# Fubarino_SD_v15.net
KiCad netlist of a schematic drawn in EAGLE
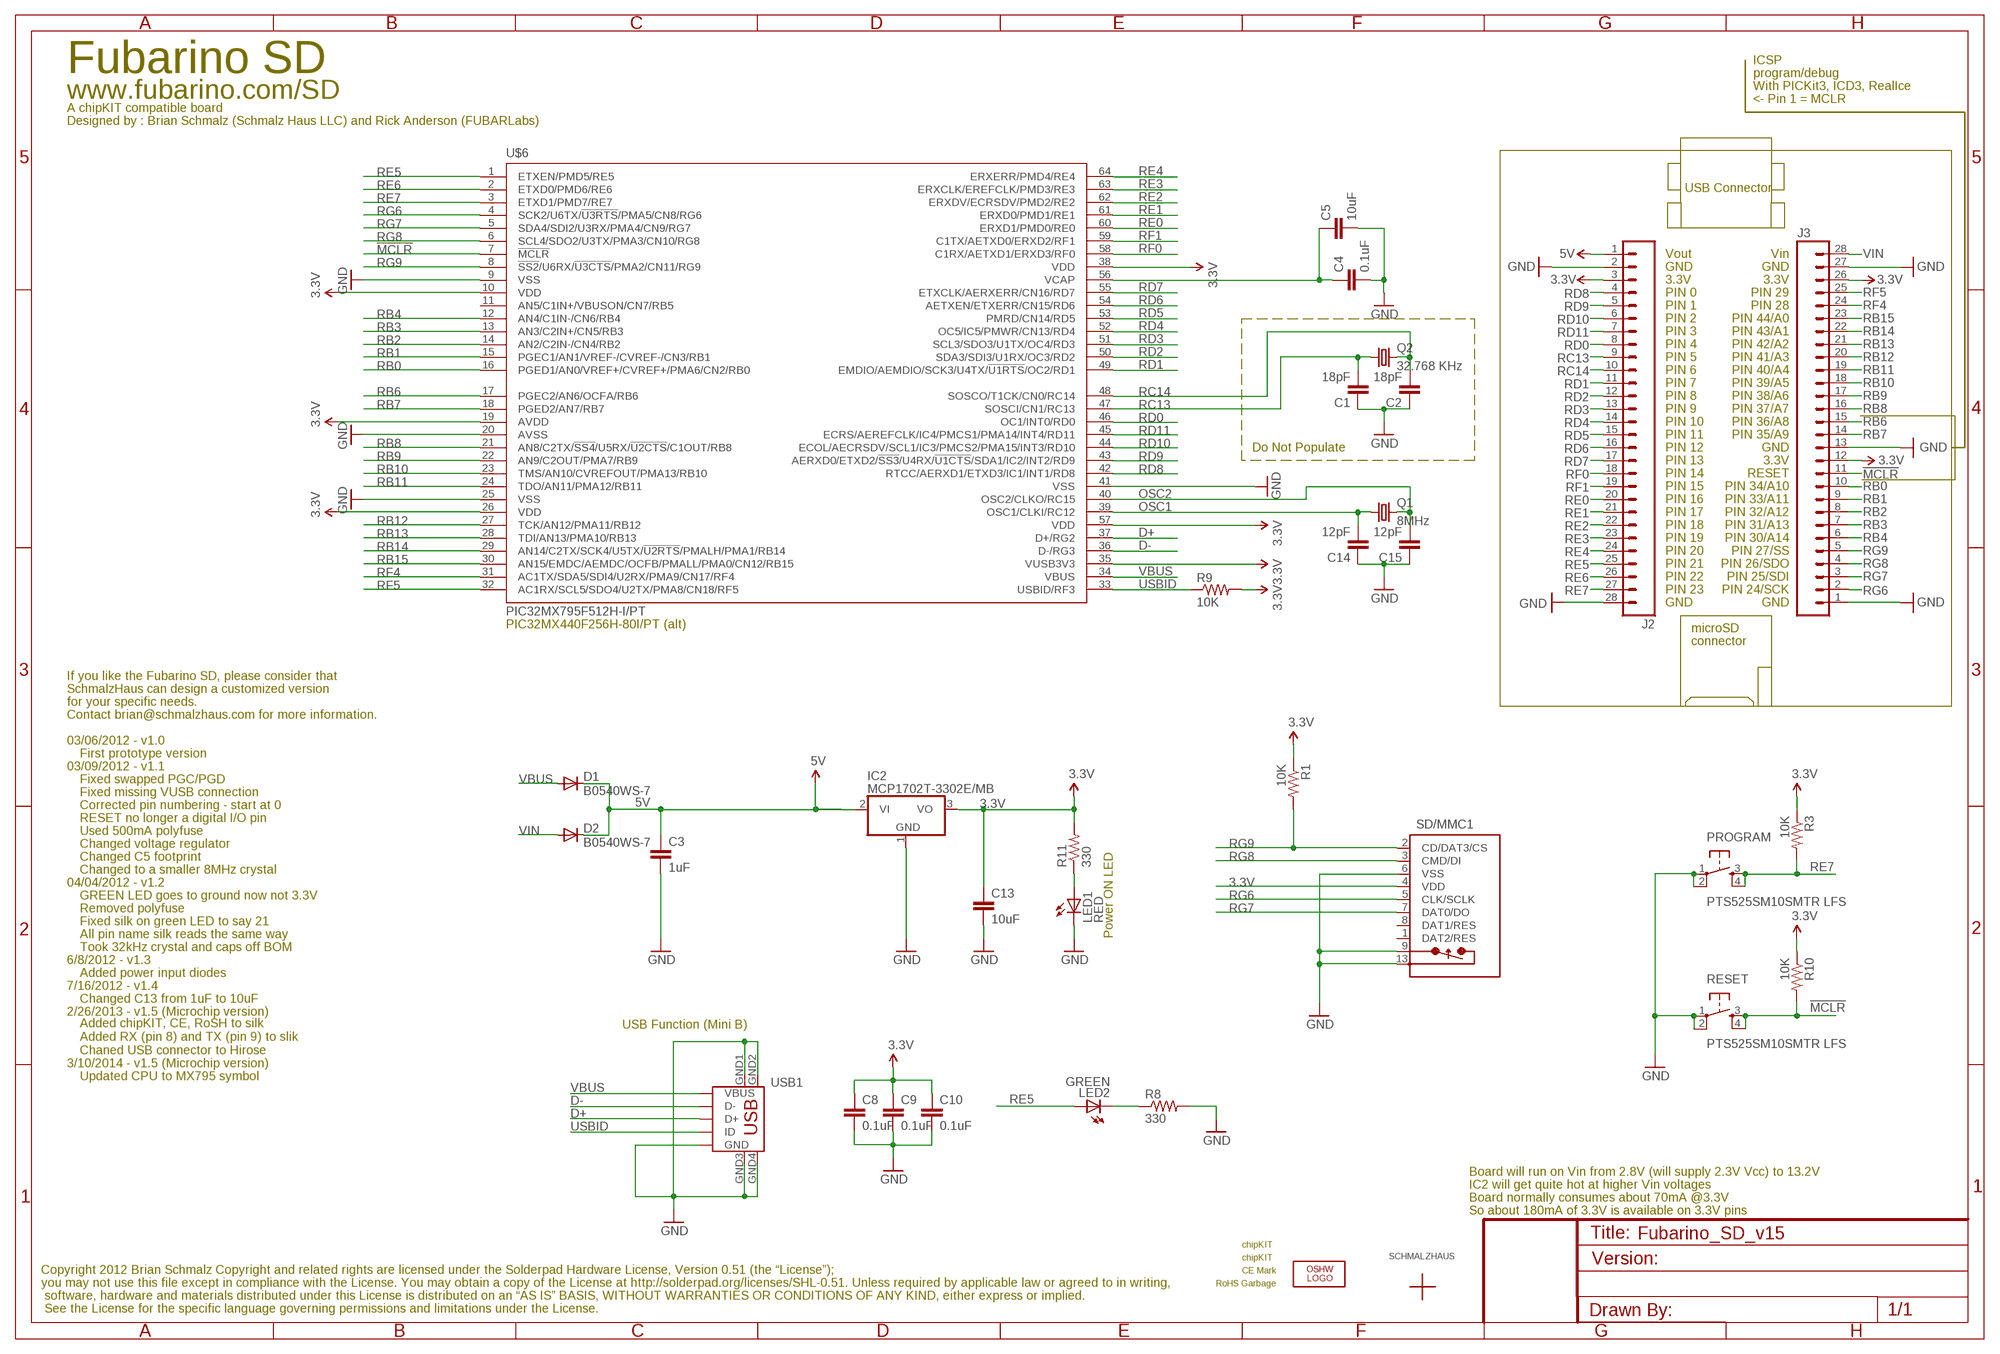
[diagram p0: schematic, sheet 1]

(export (version "E")
  (design (tool "Eeschema 10.0.6"))
  (components
    (comp (ref "C1")
      (value "18pF")
      (footprint "eagle-import:0603-CAP")
      (libsource (lib "eagle-import") (part "SparkFun_CAP0603-CAP"))
    )
    (comp (ref "C2")
      (value "18pF")
      (footprint "eagle-import:0603-CAP")
      (libsource (lib "eagle-import") (part "SparkFun_CAP0603-CAP"))
    )
    (comp (ref "C3")
      (value "1uF")
      (footprint "eagle-import:0603-CAP")
      (libsource (lib "eagle-import") (part "SparkFun_CAP0603-CAP"))
    )
    (comp (ref "C4")
      (value "0.1uF")
      (footprint "eagle-import:0603-CAP")
      (libsource (lib "eagle-import") (part "SparkFun_CAP0603-CAP"))
    )
    (comp (ref "C5")
      (value "10uF")
      (footprint "eagle-import:0805")
      (libsource (lib "eagle-import") (part "CAP0805"))
    )
    (comp (ref "C8")
      (value "0.1uF")
      (footprint "eagle-import:0603-CAP")
      (libsource (lib "eagle-import") (part "SparkFun_CAP0603-CAP"))
    )
    (comp (ref "C9")
      (value "0.1uF")
      (footprint "eagle-import:0603-CAP")
      (libsource (lib "eagle-import") (part "SparkFun_CAP0603-CAP"))
    )
    (comp (ref "C10")
      (value "0.1uF")
      (footprint "eagle-import:0603")
      (libsource (lib "eagle-import") (part "CAP0603"))
    )
    (comp (ref "C13")
      (value "10uF")
      (footprint "eagle-import:0805")
      (libsource (lib "eagle-import") (part "SparkFun02-20-08_CAP0805"))
    )
    (comp (ref "C14")
      (value "12pF")
      (footprint "eagle-import:0603-CAP")
      (libsource (lib "eagle-import") (part "SparkFun_CAP0603-CAP"))
    )
    (comp (ref "C15")
      (value "12pF")
      (footprint "eagle-import:0603-CAP")
      (libsource (lib "eagle-import") (part "SparkFun_CAP0603-CAP"))
    )
    (comp (ref "D1")
      (value "B0540WS-7")
      (footprint "eagle-import:SOD-323")
      (libsource (lib "eagle-import") (part "DIODESOD"))
    )
    (comp (ref "D2")
      (value "B0540WS-7")
      (footprint "eagle-import:SOD-323")
      (libsource (lib "eagle-import") (part "DIODESOD"))
    )
    (comp (ref "IC2")
      (value "MCP1702T-3302E/MB")
      (footprint "eagle-import:SOT89")
      (libsource (lib "eagle-import") (part "MCP1703MB33"))
    )
    (comp (ref "J2")
      (value "M28USEPIN1")
      (footprint "eagle-import:1X28")
      (libsource (lib "eagle-import") (part "M28USEPIN1"))
    )
    (comp (ref "J3")
      (value "M28NOPIN1")
      (footprint "eagle-import:1X28_NO_PIN_1")
      (libsource (lib "eagle-import") (part "M28NOPIN1"))
    )
    (comp (ref "LED1")
      (value "RED")
      (footprint "eagle-import:LED-0603")
      (libsource (lib "eagle-import") (part "LED0603"))
    )
    (comp (ref "LED2")
      (value "GREEN")
      (footprint "eagle-import:LED-0603")
      (libsource (lib "eagle-import") (part "LED0603"))
    )
    (comp (ref "LOGO1")
      (value "OSHW_LOGO_8MILX0070-NT")
      (footprint "eagle-import:OSHW_8X70_NOTEXT")
      (libsource (lib "eagle-import") (part "OSHW_LOGO_8MILX0070-NT"))
    )
    (comp (ref "PROGRAM")
      (value "PTS525SM10SMTR LFS")
      (footprint "eagle-import:TACTILE_SWITCH_SMD")
      (libsource (lib "eagle-import") (part "TAC_SWITCHSND"))
    )
    (comp (ref "Q1")
      (value "8MHz")
      (footprint "eagle-import:NX5032_5MM_3.2MM_CRYSTAL")
      (libsource (lib "eagle-import") (part "CRYSTALNX5032"))
    )
    (comp (ref "Q2")
      (value "32.768 KHz")
      (footprint "eagle-import:TC26H")
      (libsource (lib "eagle-import") (part "CRYSTALTC26H"))
    )
    (comp (ref "R1")
      (value "10K")
      (footprint "eagle-import:0603-RES")
      (libsource (lib "eagle-import") (part "RESISTOR0603-RES"))
    )
    (comp (ref "R3")
      (value "10K")
      (footprint "eagle-import:0603-RES")
      (libsource (lib "eagle-import") (part "RESISTOR0603-RES"))
    )
    (comp (ref "R8")
      (value "330")
      (footprint "eagle-import:0603-RES")
      (libsource (lib "eagle-import") (part "RESISTOR0603-RES"))
    )
    (comp (ref "R9")
      (value "10K")
      (footprint "eagle-import:0603-RES")
      (libsource (lib "eagle-import") (part "RESISTOR0603-RES"))
    )
    (comp (ref "R10")
      (value "10K")
      (footprint "eagle-import:0603-RES")
      (libsource (lib "eagle-import") (part "RESISTOR0603-RES"))
    )
    (comp (ref "R11")
      (value "330")
      (footprint "eagle-import:0603-RES")
      (libsource (lib "eagle-import") (part "RESISTOR0603-RES"))
    )
    (comp (ref "RESET")
      (value "PTS525SM10SMTR LFS")
      (footprint "eagle-import:TACTILE_SWITCH_SMD")
      (libsource (lib "eagle-import") (part "TAC_SWITCHSND"))
    )
    (comp (ref "SD/MMC1")
      (value "MICRO_SD/MMC_CP_NEWTFC-WPAPR-08")
      (footprint "eagle-import:TFC-WPAPR-08")
      (libsource (lib "eagle-import") (part "MICRO_SD/MMC_CP_NEWTFC-WPAPR-08"))
    )
    (comp (ref "U$1")
      (value "SCHMALZHAUSSCHMALZHAUS_SMALL")
      (footprint "eagle-import:SCHMALZHAUS_SMALL")
      (libsource (lib "eagle-import") (part "SCHMALZHAUSSCHMALZHAUS_SMALL"))
    )
    (comp (ref "U$2")
      (value "CE_MARK5MM")
      (footprint "eagle-import:CE_5MM")
      (libsource (lib "eagle-import") (part "CE_MARK5MM"))
    )
    (comp (ref "U$3")
      (value "ROHS_GARBAGE")
      (footprint "eagle-import:ROHS_GARBAGE_5MM")
      (libsource (lib "eagle-import") (part "ROHS_GARBAGE"))
    )
    (comp (ref "U$4")
      (value "CHIPKIT2MM")
      (footprint "eagle-import:CHIPKIT_2MM")
      (libsource (lib "eagle-import") (part "CHIPKIT2MM"))
    )
    (comp (ref "U$5")
      (value "CHIPKIT2MM")
      (footprint "eagle-import:CHIPKIT_2MM")
      (libsource (lib "eagle-import") (part "CHIPKIT2MM"))
    )
    (comp (ref "U$6")
      (value "PIC32MX795F512H-I/PT")
      (footprint "eagle-import:TQFP64-10X10")
      (libsource (lib "eagle-import") (part "PIC32MX795F512H-I/PT"))
    )
    (comp (ref "USB1")
      (value "MINI_USB9SMALLER_CREAM")
      (footprint "eagle-import:USB_MINI_9PIN-SMALLER_CREAM")
      (libsource (lib "eagle-import") (part "MINI_USB9SMALLER_CREAM"))
    )
  )
  (nets
    (net (code "1") (name "/D+") (class "Default")
      (node (ref "U$6") (pin "37") (pinfunction "D+/RG2_37") (pintype "bidirectional"))
      (node (ref "USB1") (pin "D+") (pinfunction "D+_D+") (pintype "input"))
    )
    (net (code "2") (name "/D-") (class "Default")
      (node (ref "U$6") (pin "36") (pinfunction "D-/RG3_36") (pintype "bidirectional"))
      (node (ref "USB1") (pin "D-") (pinfunction "D-_D-") (pintype "input"))
    )
    (net (code "3") (name "/OSC1") (class "Default")
      (node (ref "C14") (pin "2") (pinfunction "2_2") (pintype "passive"))
      (node (ref "Q1") (pin "1") (pinfunction "1_1") (pintype "passive"))
      (node (ref "U$6") (pin "39") (pinfunction "OSC1/CLKI/RC12_39") (pintype "bidirectional"))
    )
    (net (code "4") (name "/OSC2") (class "Default")
      (node (ref "C15") (pin "2") (pinfunction "2_2") (pintype "passive"))
      (node (ref "Q1") (pin "2") (pinfunction "2_2") (pintype "passive"))
      (node (ref "U$6") (pin "40") (pinfunction "OSC2/CLKO/RC15_40") (pintype "bidirectional"))
    )
    (net (code "5") (name "/RB0") (class "Default")
      (node (ref "J3") (pin "10") (pinfunction "10_10") (pintype "passive"))
      (node (ref "U$6") (pin "16") (pinfunction "PGED1/AN0/VREF+/CVREF+/PMA6/CN2/RB0_16") (pintype "bidirectional"))
    )
    (net (code "6") (name "/RB1") (class "Default")
      (node (ref "J3") (pin "9") (pinfunction "9_9") (pintype "passive"))
      (node (ref "U$6") (pin "15") (pinfunction "PGEC1/AN1/VREF-/CVREF-/CN3/RB1_15") (pintype "bidirectional"))
    )
    (net (code "7") (name "/RB2") (class "Default")
      (node (ref "J3") (pin "8") (pinfunction "8_8") (pintype "passive"))
      (node (ref "U$6") (pin "14") (pinfunction "AN2/C2IN-/CN4/RB2_14") (pintype "bidirectional"))
    )
    (net (code "8") (name "/RB3") (class "Default")
      (node (ref "J3") (pin "7") (pinfunction "7_7") (pintype "passive"))
      (node (ref "U$6") (pin "13") (pinfunction "AN3/C2IN+/CN5/RB3_13") (pintype "bidirectional"))
    )
    (net (code "9") (name "/RB4") (class "Default")
      (node (ref "J3") (pin "6") (pinfunction "6_6") (pintype "passive"))
      (node (ref "U$6") (pin "12") (pinfunction "AN4/C1IN-/CN6/RB4_12") (pintype "bidirectional"))
    )
    (net (code "10") (name "/RB6") (class "Default")
      (node (ref "J3") (pin "15") (pinfunction "15_15") (pintype "passive"))
      (node (ref "U$6") (pin "17") (pinfunction "PGEC2/AN6/OCFA/RB6_17") (pintype "bidirectional"))
    )
    (net (code "11") (name "/RB7") (class "Default")
      (node (ref "J3") (pin "14") (pinfunction "14_14") (pintype "passive"))
      (node (ref "U$6") (pin "18") (pinfunction "PGED2/AN7/RB7_18") (pintype "bidirectional"))
    )
    (net (code "12") (name "/RB8") (class "Default")
      (node (ref "J3") (pin "16") (pinfunction "16_16") (pintype "passive"))
      (node (ref "U$6") (pin "21") (pinfunction "AN8/C2TX/~{SS4}/U5RX/~{U2CTS}/C1OUT/RB8_21") (pintype "bidirectional"))
    )
    (net (code "13") (name "/RB9") (class "Default")
      (node (ref "J3") (pin "17") (pinfunction "17_17") (pintype "passive"))
      (node (ref "U$6") (pin "22") (pinfunction "AN9/C2OUT/PMA7/RB9_22") (pintype "bidirectional"))
    )
    (net (code "14") (name "/RB10") (class "Default")
      (node (ref "J3") (pin "18") (pinfunction "18_18") (pintype "passive"))
      (node (ref "U$6") (pin "23") (pinfunction "TMS/AN10/CVREFOUT/PMA13/RB10_23") (pintype "input"))
    )
    (net (code "15") (name "/RB11") (class "Default")
      (node (ref "J3") (pin "19") (pinfunction "19_19") (pintype "passive"))
      (node (ref "U$6") (pin "24") (pinfunction "TDO/AN11/PMA12/RB11_24") (pintype "bidirectional"))
    )
    (net (code "16") (name "/RB12") (class "Default")
      (node (ref "J3") (pin "20") (pinfunction "20_20") (pintype "passive"))
      (node (ref "U$6") (pin "27") (pinfunction "TCK/AN12/PMA11/RB12_27") (pintype "input"))
    )
    (net (code "17") (name "/RB13") (class "Default")
      (node (ref "J3") (pin "21") (pinfunction "21_21") (pintype "passive"))
      (node (ref "U$6") (pin "28") (pinfunction "TDI/AN13/PMA10/RB13_28") (pintype "input"))
    )
    (net (code "18") (name "/RB14") (class "Default")
      (node (ref "J3") (pin "22") (pinfunction "22_22") (pintype "passive"))
      (node (ref "U$6") (pin "29") (pinfunction "AN14/C2TX/SCK4/U5TX/~{U2RTS}/PMALH/PMA1/RB14_29") (pintype "bidirectional"))
    )
    (net (code "19") (name "/RB15") (class "Default")
      (node (ref "J3") (pin "23") (pinfunction "23_23") (pintype "passive"))
      (node (ref "U$6") (pin "30") (pinfunction "AN15/EMDC/AEMDC/OCFB/PMALL/PMA0/CN12/RB15_30") (pintype "bidirectional"))
    )
    (net (code "20") (name "/RC13") (class "Default")
      (node (ref "C1") (pin "2") (pinfunction "2_2") (pintype "passive"))
      (node (ref "J2") (pin "9") (pinfunction "9_9") (pintype "passive"))
      (node (ref "Q2") (pin "1") (pinfunction "1_1") (pintype "passive"))
      (node (ref "U$6") (pin "47") (pinfunction "SOSCI/CN1/RC13_47") (pintype "bidirectional"))
    )
    (net (code "21") (name "/RC14") (class "Default")
      (node (ref "C2") (pin "2") (pinfunction "2_2") (pintype "passive"))
      (node (ref "J2") (pin "10") (pinfunction "10_10") (pintype "passive"))
      (node (ref "Q2") (pin "2") (pinfunction "2_2") (pintype "passive"))
      (node (ref "U$6") (pin "48") (pinfunction "SOSCO/T1CK/CN0/RC14_48") (pintype "bidirectional"))
    )
    (net (code "22") (name "/RD0") (class "Default")
      (node (ref "J2") (pin "8") (pinfunction "8_8") (pintype "passive"))
      (node (ref "U$6") (pin "46") (pinfunction "OC1/INT0/RD0_46") (pintype "bidirectional"))
    )
    (net (code "23") (name "/RD1") (class "Default")
      (node (ref "J2") (pin "11") (pinfunction "11_11") (pintype "passive"))
      (node (ref "U$6") (pin "49") (pinfunction "EMDIO/AEMDIO/SCK3/U4TX/~{U1RTS}/OC2/RD1_49") (pintype "bidirectional"))
    )
    (net (code "24") (name "/RD2") (class "Default")
      (node (ref "J2") (pin "12") (pinfunction "12_12") (pintype "passive"))
      (node (ref "U$6") (pin "50") (pinfunction "SDA3/SDI3/U1RX/OC3/RD2_50") (pintype "bidirectional"))
    )
    (net (code "25") (name "/RD3") (class "Default")
      (node (ref "J2") (pin "13") (pinfunction "13_13") (pintype "passive"))
      (node (ref "U$6") (pin "51") (pinfunction "SCL3/SDO3/U1TX/OC4/RD3_51") (pintype "bidirectional"))
    )
    (net (code "26") (name "/RD4") (class "Default")
      (node (ref "J2") (pin "14") (pinfunction "14_14") (pintype "passive"))
      (node (ref "U$6") (pin "52") (pinfunction "OC5/IC5/PMWR/CN13/RD4_52") (pintype "bidirectional"))
    )
    (net (code "27") (name "/RD5") (class "Default")
      (node (ref "J2") (pin "15") (pinfunction "15_15") (pintype "passive"))
      (node (ref "U$6") (pin "53") (pinfunction "PMRD/CN14/RD5_53") (pintype "bidirectional"))
    )
    (net (code "28") (name "/RD6") (class "Default")
      (node (ref "J2") (pin "16") (pinfunction "16_16") (pintype "passive"))
      (node (ref "U$6") (pin "54") (pinfunction "AETXEN/ETXERR/CN15/RD6_54") (pintype "bidirectional"))
    )
    (net (code "29") (name "/RD7") (class "Default")
      (node (ref "J2") (pin "17") (pinfunction "17_17") (pintype "passive"))
      (node (ref "U$6") (pin "55") (pinfunction "ETXCLK/AERXERR/CN16/RD7_55") (pintype "bidirectional"))
    )
    (net (code "30") (name "/RD8") (class "Default")
      (node (ref "J2") (pin "4") (pinfunction "4_4") (pintype "passive"))
      (node (ref "U$6") (pin "42") (pinfunction "RTCC/AERXD1/ETXD3/IC1/INT1/RD8_42") (pintype "bidirectional"))
    )
    (net (code "31") (name "/RD9") (class "Default")
      (node (ref "J2") (pin "5") (pinfunction "5_5") (pintype "passive"))
      (node (ref "U$6") (pin "43") (pinfunction "AERXD0/ETXD2/~{SS3}/U4RX/~{U1CTS}/SDA1/IC2/INT2/RD9_43") (pintype "bidirectional"))
    )
    (net (code "32") (name "/RD10") (class "Default")
      (node (ref "J2") (pin "6") (pinfunction "6_6") (pintype "passive"))
      (node (ref "U$6") (pin "44") (pinfunction "ECOL/AECRSDV/SCL1/IC3/PMCS2/PMA15/INT3/RD10_44") (pintype "bidirectional"))
    )
    (net (code "33") (name "/RD11") (class "Default")
      (node (ref "J2") (pin "7") (pinfunction "7_7") (pintype "passive"))
      (node (ref "U$6") (pin "45") (pinfunction "ECRS/AEREFCLK/IC4/PMCS1/PMA14/INT4/RD11_45") (pintype "bidirectional"))
    )
    (net (code "34") (name "/RE0") (class "Default")
      (node (ref "J2") (pin "20") (pinfunction "20_20") (pintype "passive"))
      (node (ref "U$6") (pin "60") (pinfunction "ERXD1/PMD0/RE0_60") (pintype "bidirectional"))
    )
    (net (code "35") (name "/RE1") (class "Default")
      (node (ref "J2") (pin "21") (pinfunction "21_21") (pintype "passive"))
      (node (ref "U$6") (pin "61") (pinfunction "ERXD0/PMD1/RE1_61") (pintype "bidirectional"))
    )
    (net (code "36") (name "/RE2") (class "Default")
      (node (ref "J2") (pin "22") (pinfunction "22_22") (pintype "passive"))
      (node (ref "U$6") (pin "62") (pinfunction "ERXDV/ECRSDV/PMD2/RE2_62") (pintype "bidirectional"))
    )
    (net (code "37") (name "/RE3") (class "Default")
      (node (ref "J2") (pin "23") (pinfunction "23_23") (pintype "passive"))
      (node (ref "U$6") (pin "63") (pinfunction "ERXCLK/EREFCLK/PMD3/RE3_63") (pintype "bidirectional"))
    )
    (net (code "38") (name "/RE4") (class "Default")
      (node (ref "J2") (pin "24") (pinfunction "24_24") (pintype "passive"))
      (node (ref "U$6") (pin "64") (pinfunction "ERXERR/PMD4/RE4_64") (pintype "bidirectional"))
    )
    (net (code "39") (name "/RE5") (class "Default")
      (node (ref "J2") (pin "25") (pinfunction "25_25") (pintype "passive"))
      (node (ref "LED2") (pin "A") (pinfunction "A_A") (pintype "passive"))
      (node (ref "U$6") (pin "1") (pinfunction "ETXEN/PMD5/RE5_1") (pintype "bidirectional"))
    )
    (net (code "40") (name "/RE6") (class "Default")
      (node (ref "J2") (pin "26") (pinfunction "26_26") (pintype "passive"))
      (node (ref "U$6") (pin "2") (pinfunction "ETXD0/PMD6/RE6_2") (pintype "bidirectional"))
    )
    (net (code "41") (name "/RE7") (class "Default")
      (node (ref "J2") (pin "27") (pinfunction "27_27") (pintype "passive"))
      (node (ref "PROGRAM") (pin "3") (pinfunction "3_3") (pintype "passive"))
      (node (ref "PROGRAM") (pin "4") (pinfunction "4_4") (pintype "passive"))
      (node (ref "R3") (pin "2") (pinfunction "2_2") (pintype "passive"))
      (node (ref "U$6") (pin "3") (pinfunction "ETXD1/PMD7/RE7_3") (pintype "bidirectional"))
    )
    (net (code "42") (name "/RF0") (class "Default")
      (node (ref "J2") (pin "18") (pinfunction "18_18") (pintype "passive"))
      (node (ref "U$6") (pin "58") (pinfunction "C1RX/AETXD1/ERXD3/RF0_58") (pintype "bidirectional"))
    )
    (net (code "43") (name "/RF1") (class "Default")
      (node (ref "J2") (pin "19") (pinfunction "19_19") (pintype "passive"))
      (node (ref "U$6") (pin "59") (pinfunction "C1TX/AETXD0/ERXD2/RF1_59") (pintype "bidirectional"))
    )
    (net (code "44") (name "/RF4") (class "Default")
      (node (ref "J3") (pin "24") (pinfunction "24_24") (pintype "passive"))
      (node (ref "U$6") (pin "31") (pinfunction "AC1TX/SDA5/SDI4/U2RX/PMA9/CN17/RF4_31") (pintype "bidirectional"))
    )
    (net (code "45") (name "/RF5") (class "Default")
      (node (ref "J3") (pin "25") (pinfunction "25_25") (pintype "passive"))
      (node (ref "U$6") (pin "32") (pinfunction "AC1RX/SCL5/SDO4/U2TX/PMA8/CN18/RF5_32") (pintype "bidirectional"))
    )
    (net (code "46") (name "/RG6") (class "Default")
      (node (ref "J3") (pin "2") (pinfunction "2_2") (pintype "passive"))
      (node (ref "SD/MMC1") (pin "5") (pinfunction "CLK/SCLK_5") (pintype "input"))
      (node (ref "U$6") (pin "4") (pinfunction "SCK2/U6TX/~{U3RTS}/PMA5/CN8/RG6_4") (pintype "bidirectional"))
    )
    (net (code "47") (name "/RG7") (class "Default")
      (node (ref "J3") (pin "3") (pinfunction "3_3") (pintype "passive"))
      (node (ref "SD/MMC1") (pin "7") (pinfunction "DAT0/DO_7") (pintype "output"))
      (node (ref "U$6") (pin "5") (pinfunction "SDA4/SDI2/U3RX/PMA4/CN9/RG7_5") (pintype "bidirectional"))
    )
    (net (code "48") (name "/RG8") (class "Default")
      (node (ref "J3") (pin "4") (pinfunction "4_4") (pintype "passive"))
      (node (ref "SD/MMC1") (pin "3") (pinfunction "CMD/DI_3") (pintype "input"))
      (node (ref "U$6") (pin "6") (pinfunction "SCL4/SDO2/U3TX/PMA3/CN10/RG8_6") (pintype "bidirectional"))
    )
    (net (code "49") (name "/RG9") (class "Default")
      (node (ref "J3") (pin "5") (pinfunction "5_5") (pintype "passive"))
      (node (ref "R1") (pin "2") (pinfunction "2_2") (pintype "passive"))
      (node (ref "SD/MMC1") (pin "2") (pinfunction "CD/DAT3/CS_2") (pintype "input"))
      (node (ref "U$6") (pin "8") (pinfunction "~{SS2}/U6RX/~{U3CTS}/PMA2/CN11/RG9_8") (pintype "bidirectional"))
    )
    (net (code "50") (name "/USBID") (class "Default")
      (node (ref "R9") (pin "1") (pinfunction "1_1") (pintype "passive"))
      (node (ref "U$6") (pin "33") (pinfunction "USBID/RF3_33") (pintype "bidirectional"))
      (node (ref "USB1") (pin "ID") (pinfunction "ID_ID") (pintype "input"))
    )
    (net (code "51") (name "/VBUS") (class "Default")
      (node (ref "D1") (pin "2") (pinfunction "A_2") (pintype "passive"))
      (node (ref "U$6") (pin "34") (pinfunction "VBUS_34") (pintype "bidirectional"))
      (node (ref "USB1") (pin "VBUS") (pinfunction "VBUS_VBUS") (pintype "power_in"))
    )
    (net (code "52") (name "/VIN") (class "Default")
      (node (ref "D2") (pin "2") (pinfunction "A_2") (pintype "passive"))
      (node (ref "J3") (pin "28") (pinfunction "28_28") (pintype "passive"))
    )
    (net (code "53") (name "/~{MCLR}") (class "Default")
      (node (ref "J3") (pin "11") (pinfunction "11_11") (pintype "passive"))
      (node (ref "R10") (pin "2") (pinfunction "2_2") (pintype "passive"))
      (node (ref "RESET") (pin "3") (pinfunction "3_3") (pintype "passive"))
      (node (ref "RESET") (pin "4") (pinfunction "4_4") (pintype "passive"))
      (node (ref "U$6") (pin "7") (pinfunction "~{MCLR}_7") (pintype "input"))
    )
    (net (code "54") (name "3.3V") (class "Default")
      (node (ref "C10") (pin "1") (pinfunction "1_1") (pintype "passive"))
      (node (ref "C13") (pin "1") (pinfunction "1_1") (pintype "passive"))
      (node (ref "C8") (pin "1") (pinfunction "1_1") (pintype "passive"))
      (node (ref "C9") (pin "1") (pinfunction "1_1") (pintype "passive"))
      (node (ref "IC2") (pin "3") (pinfunction "VO_3") (pintype "passive"))
      (node (ref "J2") (pin "3") (pinfunction "3_3") (pintype "passive"))
      (node (ref "J3") (pin "12") (pinfunction "12_12") (pintype "passive"))
      (node (ref "J3") (pin "26") (pinfunction "26_26") (pintype "passive"))
      (node (ref "R1") (pin "1") (pinfunction "1_1") (pintype "passive"))
      (node (ref "R10") (pin "1") (pinfunction "1_1") (pintype "passive"))
      (node (ref "R11") (pin "2") (pinfunction "2_2") (pintype "passive"))
      (node (ref "R3") (pin "1") (pinfunction "1_1") (pintype "passive"))
      (node (ref "R9") (pin "2") (pinfunction "2_2") (pintype "passive"))
      (node (ref "SD/MMC1") (pin "4") (pinfunction "VDD_4") (pintype "power_in"))
      (node (ref "U$6") (pin "10") (pinfunction "VDD_10") (pintype "power_in"))
      (node (ref "U$6") (pin "19") (pinfunction "AVDD_19") (pintype "power_in"))
      (node (ref "U$6") (pin "26") (pinfunction "VDD_26") (pintype "power_in"))
      (node (ref "U$6") (pin "35") (pinfunction "VUSB3V3_35") (pintype "passive"))
      (node (ref "U$6") (pin "38") (pinfunction "VDD_38") (pintype "passive"))
      (node (ref "U$6") (pin "57") (pinfunction "VDD_57") (pintype "power_in"))
    )
    (net (code "55") (name "5V") (class "Default")
      (node (ref "C3") (pin "1") (pinfunction "1_1") (pintype "passive"))
      (node (ref "D1") (pin "1") (pinfunction "C_1") (pintype "passive"))
      (node (ref "D2") (pin "1") (pinfunction "C_1") (pintype "passive"))
      (node (ref "IC2") (pin "2") (pinfunction "VI_2") (pintype "input"))
      (node (ref "IC2") (pin "2@1") (pinfunction "VI1_2@1") (pintype "input"))
      (node (ref "J2") (pin "1") (pinfunction "1_1") (pintype "passive"))
    )
    (net (code "56") (name "GND") (class "Default")
      (node (ref "C1") (pin "1") (pinfunction "1_1") (pintype "passive"))
      (node (ref "C10") (pin "2") (pinfunction "2_2") (pintype "passive"))
      (node (ref "C13") (pin "2") (pinfunction "2_2") (pintype "passive"))
      (node (ref "C14") (pin "1") (pinfunction "1_1") (pintype "passive"))
      (node (ref "C15") (pin "1") (pinfunction "1_1") (pintype "passive"))
      (node (ref "C2") (pin "1") (pinfunction "1_1") (pintype "passive"))
      (node (ref "C3") (pin "2") (pinfunction "2_2") (pintype "passive"))
      (node (ref "C4") (pin "2") (pinfunction "2_2") (pintype "passive"))
      (node (ref "C5") (pin "2") (pinfunction "2_2") (pintype "passive"))
      (node (ref "C8") (pin "2") (pinfunction "2_2") (pintype "passive"))
      (node (ref "C9") (pin "2") (pinfunction "2_2") (pintype "passive"))
      (node (ref "IC2") (pin "1") (pinfunction "GND_1") (pintype "passive"))
      (node (ref "J2") (pin "2") (pinfunction "2_2") (pintype "passive"))
      (node (ref "J2") (pin "28") (pinfunction "28_28") (pintype "passive"))
      (node (ref "J3") (pin "1") (pinfunction "1_1") (pintype "passive"))
      (node (ref "J3") (pin "13") (pinfunction "13_13") (pintype "passive"))
      (node (ref "J3") (pin "27") (pinfunction "27_27") (pintype "passive"))
      (node (ref "LED1") (pin "C") (pinfunction "C_C") (pintype "passive"))
      (node (ref "PROGRAM") (pin "1") (pinfunction "1_1") (pintype "passive"))
      (node (ref "PROGRAM") (pin "2") (pinfunction "2_2") (pintype "passive"))
      (node (ref "R8") (pin "2") (pinfunction "2_2") (pintype "passive"))
      (node (ref "RESET") (pin "1") (pinfunction "1_1") (pintype "passive"))
      (node (ref "RESET") (pin "2") (pinfunction "2_2") (pintype "passive"))
      (node (ref "SD/MMC1") (pin "13") (pinfunction "PACK1_13") (pintype "bidirectional"))
      (node (ref "SD/MMC1") (pin "6") (pinfunction "VSS_6") (pintype "power_in"))
      (node (ref "SD/MMC1") (pin "9") (pinfunction "CP_E_9") (pintype "bidirectional"))
      (node (ref "U$6") (pin "20") (pinfunction "AVSS_20") (pintype "power_in"))
      (node (ref "U$6") (pin "25") (pinfunction "VSS_25") (pintype "power_in"))
      (node (ref "U$6") (pin "41") (pinfunction "VSS_41") (pintype "power_in"))
      (node (ref "U$6") (pin "9") (pinfunction "VSS_9") (pintype "power_in"))
      (node (ref "USB1") (pin "GND") (pinfunction "GND_GND") (pintype "power_in"))
      (node (ref "USB1") (pin "GND1") (pinfunction "GND1_GND1") (pintype "input"))
      (node (ref "USB1") (pin "GND2") (pinfunction "GND2_GND2") (pintype "input"))
      (node (ref "USB1") (pin "GND3") (pinfunction "GND3_GND3") (pintype "input"))
      (node (ref "USB1") (pin "GND4") (pinfunction "GND4_GND4") (pintype "input"))
    )
    (net (code "57") (name "Net-(LED1-PadA)") (class "Default")
      (node (ref "LED1") (pin "A") (pinfunction "A_A") (pintype "passive"))
      (node (ref "R11") (pin "1") (pinfunction "1_1") (pintype "passive"))
    )
    (net (code "58") (name "Net-(LED2-PadC)") (class "Default")
      (node (ref "LED2") (pin "C") (pinfunction "C_C") (pintype "passive"))
      (node (ref "R8") (pin "1") (pinfunction "1_1") (pintype "passive"))
    )
    (net (code "59") (name "Net-(U$6-VCAP)") (class "Default")
      (node (ref "C4") (pin "1") (pinfunction "1_1") (pintype "passive"))
      (node (ref "C5") (pin "1") (pinfunction "1_1") (pintype "passive"))
      (node (ref "U$6") (pin "56") (pinfunction "VCAP_56") (pintype "power_in"))
    )
    (net (code "60") (name "unconnected-(SD/MMC1-DAT1{slash}RES-Pad8)") (class "Default")
      (node (ref "SD/MMC1") (pin "8") (pinfunction "DAT1/RES_8") (pintype "bidirectional"))
    )
    (net (code "61") (name "unconnected-(SD/MMC1-DAT2{slash}RES-Pad1)") (class "Default")
      (node (ref "SD/MMC1") (pin "1") (pinfunction "DAT2/RES_1") (pintype "bidirectional"))
    )
    (net (code "62") (name "unconnected-(U$6-AN5{slash}C1IN+{slash}VBUSON{slash}CN7{slash}RB5-Pad11)") (class "Default")
      (node (ref "U$6") (pin "11") (pinfunction "AN5/C1IN+/VBUSON/CN7/RB5_11") (pintype "bidirectional"))
    )
  )
)
